# STM-Interface.net
KiCad netlist of a schematic drawn in Altium Designer
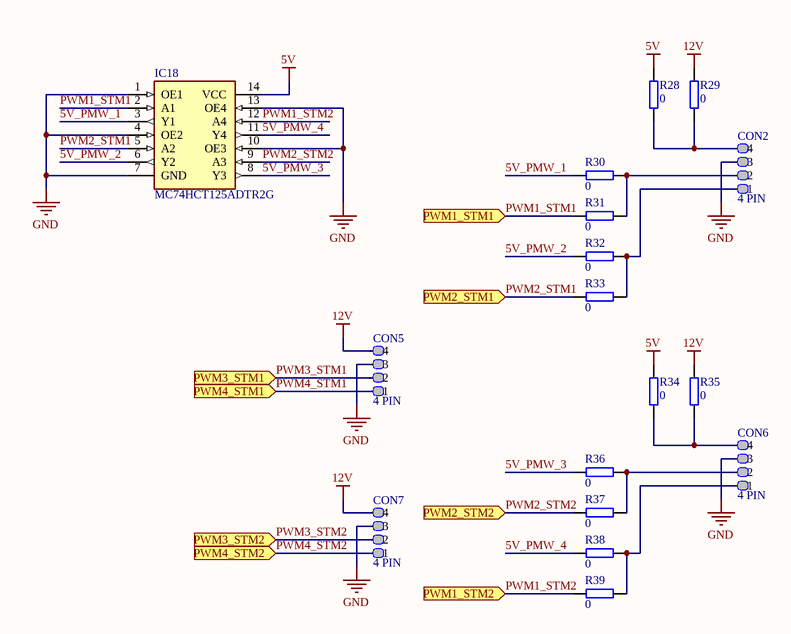
[diagram p0: STM-Interface.SchDoc]

(export (version "E")
  (design (tool "Eeschema 10.0.6"))
  (components
    (comp (ref "CON2")
      (value "4 PIN")
      (footprint "BM04B-SRSS-TB")
      (libsource (lib "Connectors") (part "4 PIN"))
    )
    (comp (ref "CON5")
      (value "4 PIN")
      (footprint "BM04B-SRSS-TB")
      (libsource (lib "Connectors") (part "4 PIN"))
    )
    (comp (ref "CON6")
      (value "4 PIN")
      (footprint "BM04B-SRSS-TB")
      (libsource (lib "Connectors") (part "4 PIN"))
    )
    (comp (ref "CON7")
      (value "4 PIN")
      (footprint "BM04B-SRSS-TB")
      (libsource (lib "Connectors") (part "4 PIN"))
    )
    (comp (ref "IC18")
      (value "MC74HCT125ADTR2G")
      (footprint "SamacSys:SOP65P640X120-14N")
      (description "Integrated Circuit")
      (fields (field (name "MOUSER PART NUMBER") "863-MC74HCT125ADTR2G"))
      (libsource (lib "*") (part "MC74HCT125ADTR2G"))
    )
    (comp (ref "R28")
      (value "0")
      (footprint "R 0402")
      (description "General pourpouse resistor")
      (libsource (lib "Components") (part "Resistor"))
    )
    (comp (ref "R29")
      (value "0")
      (footprint "R 0402")
      (description "General pourpouse resistor")
      (libsource (lib "Components") (part "Resistor"))
    )
    (comp (ref "R30")
      (value "0")
      (footprint "R 0402")
      (description "General pourpouse resistor")
      (libsource (lib "Components") (part "Resistor"))
    )
    (comp (ref "R31")
      (value "0")
      (footprint "R 0402")
      (description "General pourpouse resistor")
      (libsource (lib "Components") (part "Resistor"))
    )
    (comp (ref "R32")
      (value "0")
      (footprint "R 0402")
      (description "General pourpouse resistor")
      (libsource (lib "Components") (part "Resistor"))
    )
    (comp (ref "R33")
      (value "0")
      (footprint "R 0402")
      (description "General pourpouse resistor")
      (libsource (lib "Components") (part "Resistor"))
    )
    (comp (ref "R34")
      (value "0")
      (footprint "R 0402")
      (description "General pourpouse resistor")
      (libsource (lib "Components") (part "Resistor"))
    )
    (comp (ref "R35")
      (value "0")
      (footprint "R 0402")
      (description "General pourpouse resistor")
      (libsource (lib "Components") (part "Resistor"))
    )
    (comp (ref "R36")
      (value "0")
      (footprint "R 0402")
      (description "General pourpouse resistor")
      (libsource (lib "Components") (part "Resistor"))
    )
    (comp (ref "R37")
      (value "0")
      (footprint "R 0402")
      (description "General pourpouse resistor")
      (libsource (lib "Components") (part "Resistor"))
    )
    (comp (ref "R38")
      (value "0")
      (footprint "R 0402")
      (description "General pourpouse resistor")
      (libsource (lib "Components") (part "Resistor"))
    )
    (comp (ref "R39")
      (value "0")
      (footprint "R 0402")
      (description "General pourpouse resistor")
      (libsource (lib "Components") (part "Resistor"))
    )
  )
  (nets
    (net (code "1") (name "/5V_PMW_1") (class "Default")
      (node (ref "IC18") (pin "3") (pinfunction "Y1_3") (pintype "output"))
      (node (ref "R30") (pin "2") (pinfunction "2_2") (pintype "passive"))
    )
    (net (code "2") (name "/5V_PMW_2") (class "Default")
      (node (ref "IC18") (pin "6") (pinfunction "Y2_6") (pintype "output"))
      (node (ref "R32") (pin "2") (pinfunction "2_2") (pintype "passive"))
    )
    (net (code "3") (name "/5V_PMW_3") (class "Default")
      (node (ref "IC18") (pin "8") (pinfunction "Y3_8") (pintype "output"))
      (node (ref "R36") (pin "2") (pinfunction "2_2") (pintype "passive"))
    )
    (net (code "4") (name "/5V_PMW_4") (class "Default")
      (node (ref "IC18") (pin "11") (pinfunction "Y4_11") (pintype "output"))
      (node (ref "R38") (pin "2") (pinfunction "2_2") (pintype "passive"))
    )
    (net (code "5") (name "/PWM1_STM1") (class "Default")
      (node (ref "IC18") (pin "2") (pinfunction "A1_2") (pintype "input"))
      (node (ref "R31") (pin "2") (pinfunction "2_2") (pintype "passive"))
    )
    (net (code "6") (name "/PWM1_STM2") (class "Default")
      (node (ref "IC18") (pin "12") (pinfunction "A4_12") (pintype "input"))
      (node (ref "R39") (pin "2") (pinfunction "2_2") (pintype "passive"))
    )
    (net (code "7") (name "/PWM2_STM1") (class "Default")
      (node (ref "IC18") (pin "5") (pinfunction "A2_5") (pintype "input"))
      (node (ref "R33") (pin "2") (pinfunction "2_2") (pintype "passive"))
    )
    (net (code "8") (name "/PWM2_STM2") (class "Default")
      (node (ref "IC18") (pin "9") (pinfunction "A3_9") (pintype "input"))
      (node (ref "R37") (pin "2") (pinfunction "2_2") (pintype "passive"))
    )
    (net (code "9") (name "/PWM3_STM1") (class "Default")
      (node (ref "CON5") (pin "2") (pinfunction "2_2") (pintype "passive"))
    )
    (net (code "10") (name "/PWM3_STM2") (class "Default")
      (node (ref "CON7") (pin "2") (pinfunction "2_2") (pintype "passive"))
    )
    (net (code "11") (name "/PWM4_STM1") (class "Default")
      (node (ref "CON5") (pin "1") (pinfunction "1_1") (pintype "passive"))
    )
    (net (code "12") (name "/PWM4_STM2") (class "Default")
      (node (ref "CON7") (pin "1") (pinfunction "1_1") (pintype "passive"))
    )
    (net (code "13") (name "5V") (class "Default")
      (node (ref "IC18") (pin "14") (pinfunction "VCC_14") (pintype "power_in"))
      (node (ref "R28") (pin "2") (pinfunction "2_2") (pintype "passive"))
      (node (ref "R34") (pin "2") (pinfunction "2_2") (pintype "passive"))
    )
    (net (code "14") (name "12V") (class "Default")
      (node (ref "CON5") (pin "4") (pinfunction "4_4") (pintype "passive"))
      (node (ref "CON7") (pin "4") (pinfunction "4_4") (pintype "passive"))
      (node (ref "R29") (pin "2") (pinfunction "2_2") (pintype "passive"))
      (node (ref "R35") (pin "2") (pinfunction "2_2") (pintype "passive"))
    )
    (net (code "15") (name "GND") (class "Default")
      (node (ref "CON2") (pin "3") (pinfunction "3_3") (pintype "passive"))
      (node (ref "CON5") (pin "3") (pinfunction "3_3") (pintype "passive"))
      (node (ref "CON6") (pin "3") (pinfunction "3_3") (pintype "passive"))
      (node (ref "CON7") (pin "3") (pinfunction "3_3") (pintype "passive"))
      (node (ref "IC18") (pin "1") (pinfunction "OE1_1") (pintype "input"))
      (node (ref "IC18") (pin "10") (pinfunction "OE3_10") (pintype "input"))
      (node (ref "IC18") (pin "13") (pinfunction "OE4_13") (pintype "input"))
      (node (ref "IC18") (pin "4") (pinfunction "OE2_4") (pintype "input"))
      (node (ref "IC18") (pin "7") (pinfunction "GND_7") (pintype "power_in"))
    )
    (net (code "16") (name "Net-(CON2-Pad1)") (class "Default")
      (node (ref "CON2") (pin "1") (pinfunction "1_1") (pintype "passive"))
      (node (ref "R32") (pin "1") (pinfunction "1_1") (pintype "passive"))
      (node (ref "R33") (pin "1") (pinfunction "1_1") (pintype "passive"))
    )
    (net (code "17") (name "Net-(CON2-Pad2)") (class "Default")
      (node (ref "CON2") (pin "2") (pinfunction "2_2") (pintype "passive"))
      (node (ref "R30") (pin "1") (pinfunction "1_1") (pintype "passive"))
      (node (ref "R31") (pin "1") (pinfunction "1_1") (pintype "passive"))
    )
    (net (code "18") (name "Net-(CON2-Pad4)") (class "Default")
      (node (ref "CON2") (pin "4") (pinfunction "4_4") (pintype "passive"))
      (node (ref "R28") (pin "1") (pinfunction "1_1") (pintype "passive"))
      (node (ref "R29") (pin "1") (pinfunction "1_1") (pintype "passive"))
    )
    (net (code "19") (name "Net-(CON6-Pad1)") (class "Default")
      (node (ref "CON6") (pin "1") (pinfunction "1_1") (pintype "passive"))
      (node (ref "R38") (pin "1") (pinfunction "1_1") (pintype "passive"))
      (node (ref "R39") (pin "1") (pinfunction "1_1") (pintype "passive"))
    )
    (net (code "20") (name "Net-(CON6-Pad2)") (class "Default")
      (node (ref "CON6") (pin "2") (pinfunction "2_2") (pintype "passive"))
      (node (ref "R36") (pin "1") (pinfunction "1_1") (pintype "passive"))
      (node (ref "R37") (pin "1") (pinfunction "1_1") (pintype "passive"))
    )
    (net (code "21") (name "Net-(CON6-Pad4)") (class "Default")
      (node (ref "CON6") (pin "4") (pinfunction "4_4") (pintype "passive"))
      (node (ref "R34") (pin "1") (pinfunction "1_1") (pintype "passive"))
      (node (ref "R35") (pin "1") (pinfunction "1_1") (pintype "passive"))
    )
  )
)
